# Analog1.net
KiCad netlist of a schematic drawn in Altium Designer
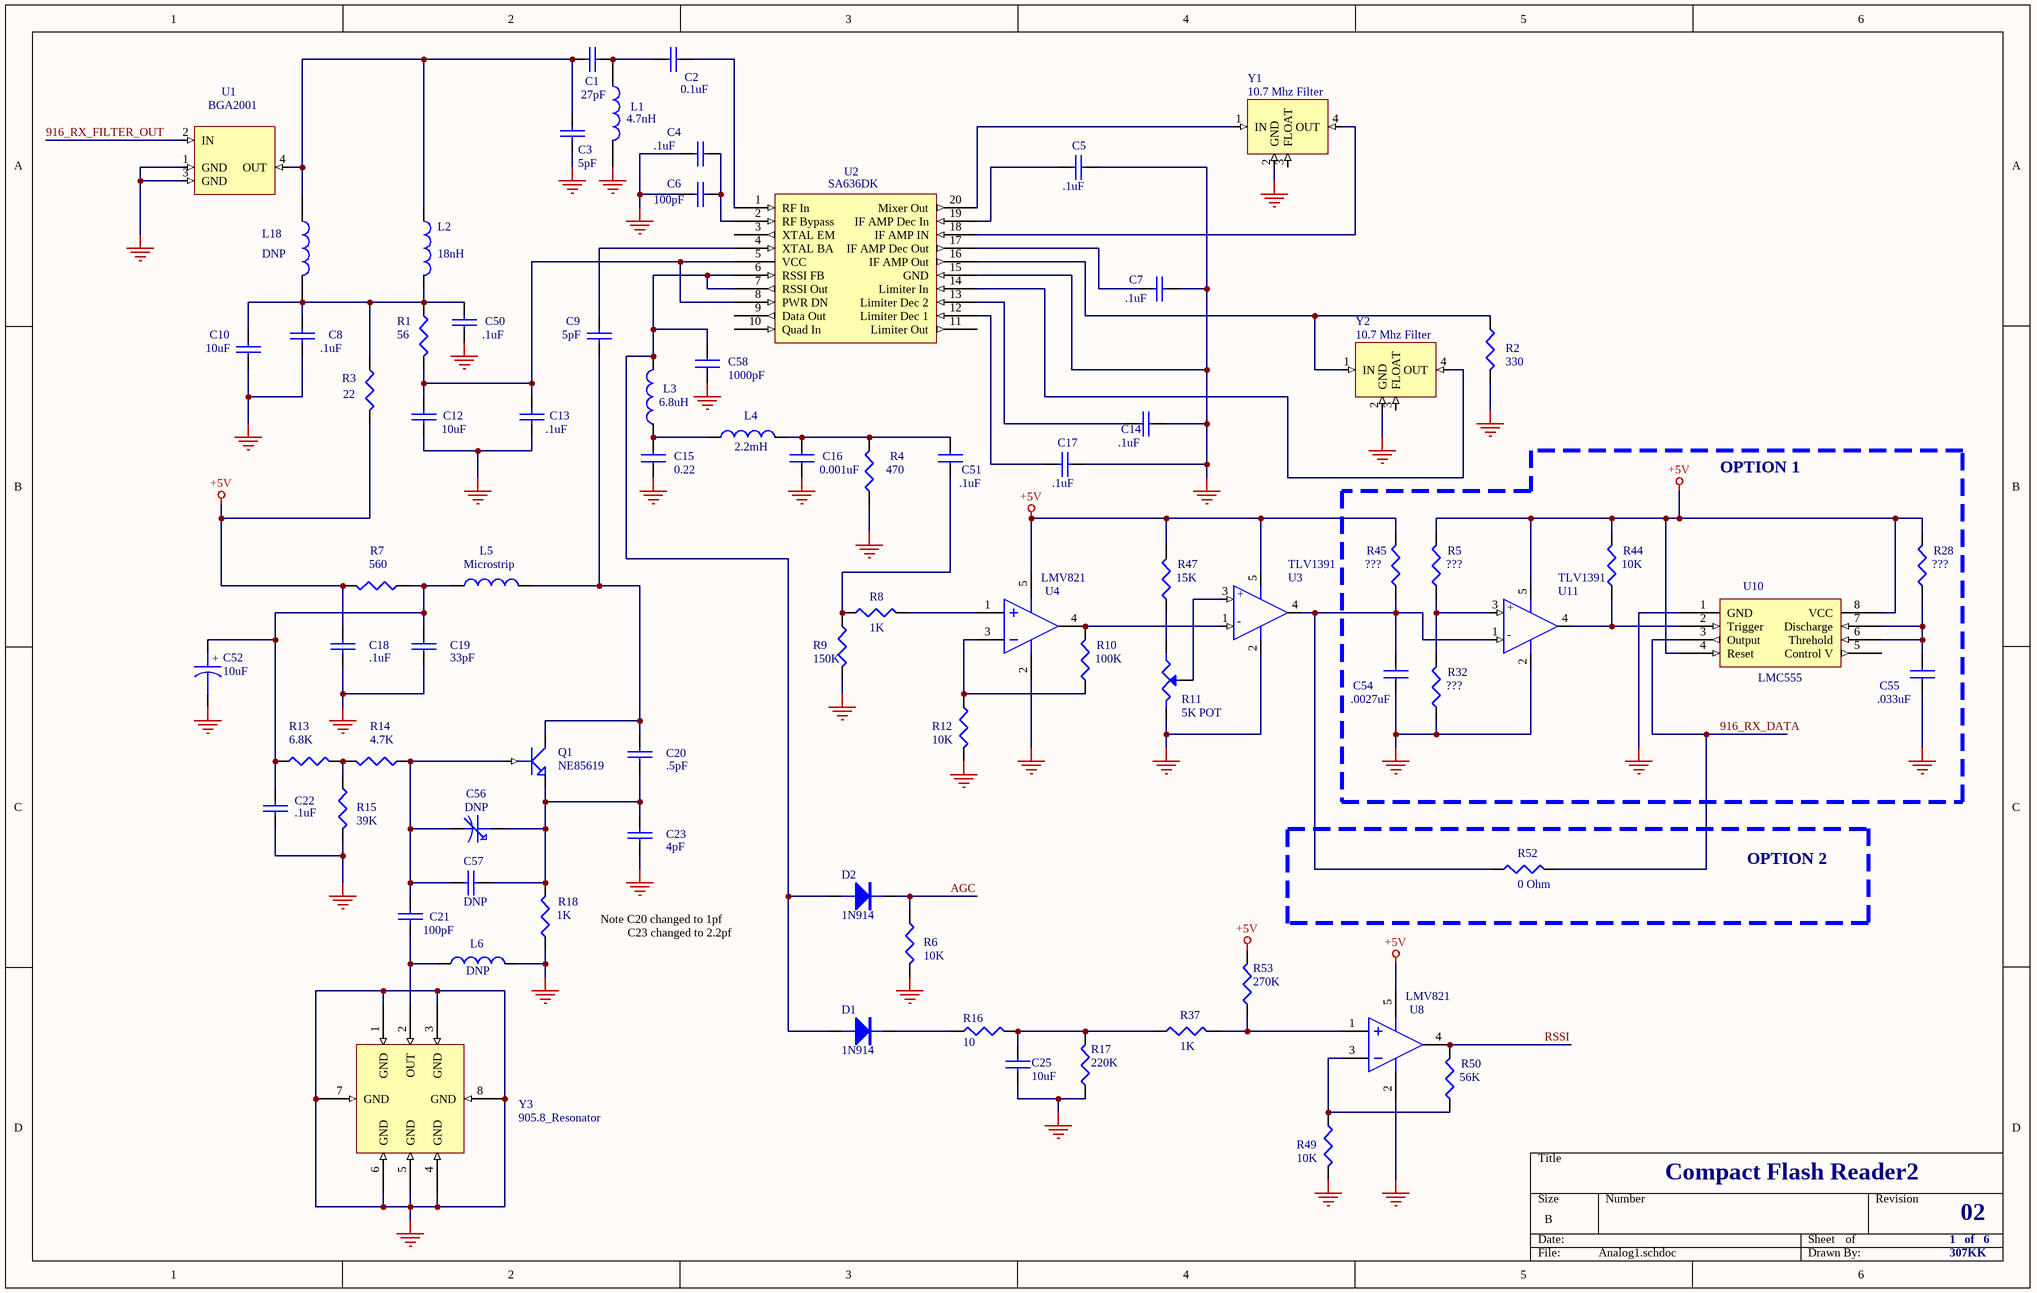
[diagram p0: Analog1.schdoc]

(export (version "E")
  (design (tool "Eeschema 10.0.6"))
  (components
    (comp (ref "C1") (value "27pF") (description "Capacitor") (libsource (lib "*") (part "CAP")))
    (comp (ref "C2") (value "0.1uF") (description "Capacitor") (libsource (lib "*") (part "CAP")))
    (comp (ref "C3") (value "5pF") (description "Capacitor") (libsource (lib "*") (part "CAP")))
    (comp (ref "C4")
      (value ".1uF")
      (footprint "0603")
      (description "Capacitor")
      (libsource (lib "*") (part "CAP"))
    )
    (comp (ref "C5")
      (value ".1uF")
      (footprint "0603")
      (description "Capacitor")
      (libsource (lib "*") (part "CAP"))
    )
    (comp (ref "C6")
      (value "100pF")
      (footprint "0603")
      (description "Capacitor")
      (libsource (lib "*") (part "CAP"))
    )
    (comp (ref "C7")
      (value ".1uF")
      (footprint "0603")
      (description "Capacitor")
      (libsource (lib "*") (part "CAP"))
    )
    (comp (ref "C8")
      (value ".1uF")
      (footprint "0603")
      (description "Capacitor")
      (libsource (lib "*") (part "CAP"))
    )
    (comp (ref "C9")
      (value "5pF")
      (footprint "0603")
      (description "Capacitor")
      (libsource (lib "*") (part "CAP"))
    )
    (comp (ref "C10")
      (value "10uF")
      (footprint "CAP A CASE")
      (description "Capacitor")
      (libsource (lib "*") (part "CAP"))
    )
    (comp (ref "C12")
      (value "10uF")
      (footprint "CAP A CASE")
      (description "Capacitor")
      (libsource (lib "*") (part "CAP"))
    )
    (comp (ref "C13")
      (value ".1uF")
      (footprint "0603")
      (description "Capacitor")
      (libsource (lib "*") (part "CAP"))
    )
    (comp (ref "C14")
      (value ".1uF")
      (footprint "0603")
      (description "Capacitor")
      (libsource (lib "*") (part "CAP"))
    )
    (comp (ref "C15") (value "0.22") (footprint "0603") (libsource (lib "*") (part "CAP_NP")))
    (comp (ref "C16") (value "0.001uF") (footprint "0603") (libsource (lib "*") (part "CAP_NP")))
    (comp (ref "C17")
      (value ".1uF")
      (footprint "0603")
      (description "Capacitor")
      (libsource (lib "*") (part "CAP"))
    )
    (comp (ref "C18")
      (value ".1uF")
      (footprint "0603")
      (description "Capacitor")
      (libsource (lib "*") (part "CAP"))
    )
    (comp (ref "C19")
      (value "33pF")
      (footprint "0603")
      (description "Capacitor")
      (libsource (lib "*") (part "CAP"))
    )
    (comp (ref "C20")
      (value ".5pF")
      (footprint "0603")
      (description "Capacitor")
      (libsource (lib "*") (part "CAP"))
    )
    (comp (ref "C21")
      (value "100pF")
      (footprint "0603")
      (description "Capacitor")
      (libsource (lib "*") (part "CAP"))
    )
    (comp (ref "C22")
      (value ".1uF")
      (footprint "0603")
      (description "Capacitor")
      (libsource (lib "*") (part "CAP"))
    )
    (comp (ref "C23")
      (value "4pF")
      (footprint "0603")
      (description "Capacitor")
      (libsource (lib "*") (part "CAP"))
    )
    (comp (ref "C25") (value "10uF") (footprint "CAP A CASE") (libsource (lib "*") (part "CAP_NP")))
    (comp (ref "C50")
      (value ".1uF")
      (footprint "0603")
      (description "Capacitor")
      (libsource (lib "*") (part "CAP"))
    )
    (comp (ref "C51") (value ".1uF") (footprint "0603") (libsource (lib "*") (part "CAP_NP")))
    (comp (ref "C52")
      (value "10uF")
      (footprint "CAP A CASE")
      (description "Capacitor")
      (libsource (lib "*") (part "CAPACITOR POL"))
    )
    (comp (ref "C54") (value ".0027uF") (footprint "0603") (libsource (lib "*") (part "CAP_NP")))
    (comp (ref "C55") (value ".033uF") (footprint "0805") (libsource (lib "*") (part "CAP_NP")))
    (comp (ref "C56")
      (value "DNP")
      (footprint "CAP TRIMMER JOHANSON")
      (libsource (lib "*") (part "CAPACITOR VAR"))
    )
    (comp (ref "C57")
      (value "DNP")
      (footprint "0603")
      (description "Capacitor")
      (libsource (lib "*") (part "CAP"))
    )
    (comp (ref "C58") (value "1000pF") (footprint "0603") (libsource (lib "*") (part "CAP_NP")))
    (comp (ref "D1")
      (value "1N914")
      (footprint "SOT23 DIODE")
      (description "Diode")
      (libsource (lib "*") (part "DIODE"))
    )
    (comp (ref "D2")
      (value "1N914")
      (footprint "SOT23 DIODE")
      (description "Diode")
      (libsource (lib "*") (part "DIODE"))
    )
    (comp (ref "L1") (value "4.7nH") (libsource (lib "*") (part "INDUCTOR")))
    (comp (ref "L2") (value "18nH") (footprint "0603") (libsource (lib "") (part "INDUCTOR_1")))
    (comp (ref "L3") (value "6.8uH") (footprint "0805") (libsource (lib "") (part "INDUCTOR_1")))
    (comp (ref "L4") (value "2.2mH") (footprint "COIL TKS5540CT-ND") (libsource (lib "") (part "INDUCTOR_1")))
    (comp (ref "L5") (value "Microstrip") (footprint "MICROSTRIP") (libsource (lib "") (part "INDUCTOR_1")))
    (comp (ref "L6") (value "DNP") (footprint "0603") (libsource (lib "") (part "INDUCTOR_1")))
    (comp (ref "L18") (value "DNP") (libsource (lib "*") (part "INDUCTOR")))
    (comp (ref "Q1")
      (value "NE85619")
      (footprint "3 PIN ULTRA SUPER MINI MOLD")
      (description "NPN Transistor")
      (libsource (lib "*") (part "NPN1"))
    )
    (comp (ref "R1") (value "56") (footprint "0603") (libsource (lib "*") (part "R")))
    (comp (ref "R2") (value "330") (footprint "0603") (libsource (lib "*") (part "R")))
    (comp (ref "R3") (value "22") (footprint "0603") (libsource (lib "*") (part "R")))
    (comp (ref "R4") (value "470") (footprint "0603") (libsource (lib "*") (part "R")))
    (comp (ref "R5") (value "???") (footprint "0603") (libsource (lib "*") (part "R")))
    (comp (ref "R6") (value "10K") (footprint "0603") (libsource (lib "*") (part "R")))
    (comp (ref "R7") (value "560") (footprint "0603") (libsource (lib "*") (part "RESISTOR")))
    (comp (ref "R8") (value "1K") (footprint "0603") (libsource (lib "*") (part "R")))
    (comp (ref "R9") (value "150K") (footprint "0603") (libsource (lib "*") (part "R")))
    (comp (ref "R10") (value "100K") (footprint "0603") (libsource (lib "*") (part "R")))
    (comp (ref "R11")
      (value "5K POT")
      (footprint "POT PANA EVN5")
      (description "Potentiometer")
      (libsource (lib "*") (part "POT1"))
    )
    (comp (ref "R12") (value "10K") (footprint "0603") (libsource (lib "*") (part "R")))
    (comp (ref "R13") (value "6.8K") (footprint "0603") (libsource (lib "*") (part "RESISTOR")))
    (comp (ref "R14") (value "4.7K") (footprint "0603") (libsource (lib "*") (part "RESISTOR")))
    (comp (ref "R15") (value "39K") (footprint "0603") (libsource (lib "*") (part "RESISTOR")))
    (comp (ref "R16") (value "10") (footprint "0603") (libsource (lib "*") (part "R")))
    (comp (ref "R17") (value "220K") (footprint "0603") (libsource (lib "*") (part "R")))
    (comp (ref "R18") (value "1K") (footprint "0603") (libsource (lib "*") (part "RESISTOR")))
    (comp (ref "R28") (value "???") (footprint "0603") (libsource (lib "*") (part "R")))
    (comp (ref "R32") (value "???") (footprint "0603") (libsource (lib "*") (part "R")))
    (comp (ref "R37") (value "1K") (footprint "0603") (libsource (lib "*") (part "R")))
    (comp (ref "R44") (value "10K") (footprint "0603") (libsource (lib "*") (part "R")))
    (comp (ref "R45") (value "???") (footprint "0603") (libsource (lib "*") (part "R")))
    (comp (ref "R47") (value "15K") (footprint "0603") (libsource (lib "*") (part "R")))
    (comp (ref "R49") (value "10K") (footprint "0603") (libsource (lib "*") (part "R")))
    (comp (ref "R50") (value "56K") (footprint "0603") (libsource (lib "*") (part "R")))
    (comp (ref "R52") (value "0 Ohm") (footprint "0603") (libsource (lib "*") (part "R")))
    (comp (ref "R53") (value "270K") (footprint "0603") (libsource (lib "*") (part "R")))
    (comp (ref "U1") (value "BGA2001") (footprint "SOT343") (libsource (lib "*") (part "BGA2001")))
    (comp (ref "U2") (value "SA636DK") (footprint "SSOP20") (libsource (lib "*") (part "SA636DK")))
    (comp (ref "U3") (value "TLV1391") (footprint "SOT25") (libsource (lib "*") (part "TLV1391")))
    (comp (ref "U4") (value "LMV821") (footprint "SOT25") (libsource (lib "*") (part "OPAMP1")))
    (comp (ref "U8") (value "LMV821") (footprint "SOT25") (libsource (lib "*") (part "OPAMP1")))
    (comp (ref "U10") (value "LMC555") (footprint "SO8 SMALL") (libsource (lib "*") (part "LMC555")))
    (comp (ref "U11") (value "TLV1391") (footprint "SOT25") (libsource (lib "*") (part "TLV1391")))
    (comp (ref "Y1") (value "10.7 Mhz Filter") (footprint "FILTER2") (libsource (lib "*") (part "FILTER2")))
    (comp (ref "Y2") (value "10.7 Mhz Filter") (footprint "FILTER2") (libsource (lib "*") (part "FILTER2")))
    (comp (ref "Y3")
      (value "905.8_Resonator")
      (footprint "RESONATOR2")
      (libsource (lib "Compact Flash Reader2") (part "RESONATOR2"))
    )
  )
  (nets
    (net (code "1") (name "+5V") (class "Default")
      (node (ref "C18") (pin "1") (pinfunction "1_1") (pintype "passive"))
      (node (ref "R28") (pin "2") (pinfunction "2_2") (pintype "passive"))
      (node (ref "R3") (pin "2") (pinfunction "2_2") (pintype "passive"))
      (node (ref "R44") (pin "2") (pinfunction "2_2") (pintype "passive"))
      (node (ref "R45") (pin "2") (pinfunction "2_2") (pintype "passive"))
      (node (ref "R47") (pin "2") (pinfunction "2_2") (pintype "passive"))
      (node (ref "R5") (pin "2") (pinfunction "2_2") (pintype "passive"))
      (node (ref "R53") (pin "2") (pinfunction "2_2") (pintype "passive"))
      (node (ref "R7") (pin "2") (pinfunction "2_2") (pintype "passive"))
      (node (ref "U10") (pin "4") (pinfunction "Reset_4") (pintype "input"))
      (node (ref "U10") (pin "8") (pinfunction "VCC_8") (pintype "power_in"))
      (node (ref "U11") (pin "5") (pinfunction "VDD_5") (pintype "power_in"))
      (node (ref "U3") (pin "5") (pinfunction "VDD_5") (pintype "power_in"))
      (node (ref "U4") (pin "5") (pinfunction "5_5") (pintype "passive"))
      (node (ref "U8") (pin "5") (pinfunction "5_5") (pintype "passive"))
    )
    (net (code "2") (name "/916_RX_DATA") (class "Default")
      (node (ref "R52") (pin "2") (pinfunction "2_2") (pintype "passive"))
      (node (ref "U10") (pin "3") (pinfunction "Output_3") (pintype "output"))
    )
    (net (code "3") (name "/916_RX_FILTER_OUT") (class "Default")
      (node (ref "U1") (pin "2") (pinfunction "IN_2") (pintype "input"))
    )
    (net (code "4") (name "/AGC") (class "Default")
      (node (ref "D2") (pin "K") (pinfunction "K_K") (pintype "passive"))
      (node (ref "R6") (pin "1") (pinfunction "1_1") (pintype "passive"))
    )
    (net (code "5") (name "/RSSI") (class "Default")
      (node (ref "R50") (pin "2") (pinfunction "2_2") (pintype "passive"))
      (node (ref "U8") (pin "4") (pinfunction "4_4") (pintype "passive"))
    )
    (net (code "6") (name "GND_SIGNAL") (class "Default")
      (node (ref "C10") (pin "2") (pinfunction "2_2") (pintype "passive"))
      (node (ref "C12") (pin "2") (pinfunction "2_2") (pintype "passive"))
      (node (ref "C13") (pin "2") (pinfunction "2_2") (pintype "passive"))
      (node (ref "C14") (pin "2") (pinfunction "2_2") (pintype "passive"))
      (node (ref "C15") (pin "1") (pinfunction "1_1") (pintype "passive"))
      (node (ref "C16") (pin "1") (pinfunction "1_1") (pintype "passive"))
      (node (ref "C17") (pin "2") (pinfunction "2_2") (pintype "passive"))
      (node (ref "C18") (pin "2") (pinfunction "2_2") (pintype "passive"))
      (node (ref "C19") (pin "2") (pinfunction "2_2") (pintype "passive"))
      (node (ref "C22") (pin "2") (pinfunction "2_2") (pintype "passive"))
      (node (ref "C23") (pin "2") (pinfunction "2_2") (pintype "passive"))
      (node (ref "C25") (pin "2") (pinfunction "2_2") (pintype "passive"))
      (node (ref "C3") (pin "2") (pinfunction "2_2") (pintype "passive"))
      (node (ref "C4") (pin "1") (pinfunction "1_1") (pintype "passive"))
      (node (ref "C5") (pin "2") (pinfunction "2_2") (pintype "passive"))
      (node (ref "C50") (pin "2") (pinfunction "2_2") (pintype "passive"))
      (node (ref "C52") (pin "2") (pinfunction "2_2") (pintype "passive"))
      (node (ref "C54") (pin "1") (pinfunction "1_1") (pintype "passive"))
      (node (ref "C55") (pin "1") (pinfunction "1_1") (pintype "passive"))
      (node (ref "C58") (pin "1") (pinfunction "1_1") (pintype "passive"))
      (node (ref "C6") (pin "1") (pinfunction "1_1") (pintype "passive"))
      (node (ref "C7") (pin "2") (pinfunction "2_2") (pintype "passive"))
      (node (ref "C8") (pin "2") (pinfunction "2_2") (pintype "passive"))
      (node (ref "L1") (pin "2") (pinfunction "2_2") (pintype "passive"))
      (node (ref "L6") (pin "2") (pinfunction "2_2") (pintype "passive"))
      (node (ref "R11") (pin "3") (pinfunction "3_3") (pintype "passive"))
      (node (ref "R12") (pin "2") (pinfunction "2_2") (pintype "passive"))
      (node (ref "R15") (pin "2") (pinfunction "2_2") (pintype "passive"))
      (node (ref "R17") (pin "2") (pinfunction "2_2") (pintype "passive"))
      (node (ref "R18") (pin "1") (pinfunction "1_1") (pintype "passive"))
      (node (ref "R2") (pin "2") (pinfunction "2_2") (pintype "passive"))
      (node (ref "R32") (pin "1") (pinfunction "1_1") (pintype "passive"))
      (node (ref "R4") (pin "1") (pinfunction "1_1") (pintype "passive"))
      (node (ref "R49") (pin "2") (pinfunction "2_2") (pintype "passive"))
      (node (ref "R6") (pin "2") (pinfunction "2_2") (pintype "passive"))
      (node (ref "R9") (pin "2") (pinfunction "2_2") (pintype "passive"))
      (node (ref "U1") (pin "1") (pinfunction "GND_1") (pintype "input"))
      (node (ref "U1") (pin "3") (pinfunction "GND_3") (pintype "input"))
      (node (ref "U10") (pin "1") (pinfunction "GND_1") (pintype "power_in"))
      (node (ref "U11") (pin "2") (pinfunction "VSS_2") (pintype "power_in"))
      (node (ref "U2") (pin "15") (pinfunction "GND_15") (pintype "input"))
      (node (ref "U3") (pin "2") (pinfunction "VSS_2") (pintype "power_in"))
      (node (ref "U4") (pin "2") (pinfunction "2_2") (pintype "passive"))
      (node (ref "U8") (pin "2") (pinfunction "2_2") (pintype "passive"))
      (node (ref "Y1") (pin "2") (pinfunction "GND_2") (pintype "input"))
      (node (ref "Y2") (pin "2") (pinfunction "GND_2") (pintype "input"))
      (node (ref "Y3") (pin "1") (pinfunction "GND_1") (pintype "input"))
      (node (ref "Y3") (pin "3") (pinfunction "GND_3") (pintype "input"))
      (node (ref "Y3") (pin "4") (pinfunction "GND_4") (pintype "input"))
      (node (ref "Y3") (pin "5") (pinfunction "GND_5") (pintype "input"))
      (node (ref "Y3") (pin "6") (pinfunction "GND_6") (pintype "input"))
      (node (ref "Y3") (pin "7") (pinfunction "GND_7") (pintype "input"))
      (node (ref "Y3") (pin "8") (pinfunction "GND_8") (pintype "input"))
    )
    (net (code "7") (name "Net-(C1-Pad2)") (class "Default")
      (node (ref "C1") (pin "2") (pinfunction "2_2") (pintype "passive"))
      (node (ref "C2") (pin "1") (pinfunction "1_1") (pintype "passive"))
      (node (ref "L1") (pin "1") (pinfunction "1_1") (pintype "passive"))
    )
    (net (code "8") (name "Net-(C10-Pad1)") (class "Default")
      (node (ref "C10") (pin "1") (pinfunction "1_1") (pintype "passive"))
      (node (ref "C50") (pin "1") (pinfunction "1_1") (pintype "passive"))
      (node (ref "C8") (pin "1") (pinfunction "1_1") (pintype "passive"))
      (node (ref "L18") (pin "2") (pinfunction "2_2") (pintype "passive"))
      (node (ref "L2") (pin "2") (pinfunction "2_2") (pintype "passive"))
      (node (ref "R1") (pin "1") (pinfunction "1_1") (pintype "passive"))
      (node (ref "R3") (pin "1") (pinfunction "1_1") (pintype "passive"))
    )
    (net (code "9") (name "Net-(C15-Pad2)") (class "Default")
      (node (ref "C15") (pin "2") (pinfunction "2_2") (pintype "passive"))
      (node (ref "L3") (pin "1") (pinfunction "1_1") (pintype "passive"))
      (node (ref "L4") (pin "1") (pinfunction "1_1") (pintype "passive"))
    )
    (net (code "10") (name "Net-(C16-Pad2)") (class "Default")
      (node (ref "C16") (pin "2") (pinfunction "2_2") (pintype "passive"))
      (node (ref "C51") (pin "2") (pinfunction "2_2") (pintype "passive"))
      (node (ref "L4") (pin "2") (pinfunction "2_2") (pintype "passive"))
      (node (ref "R4") (pin "2") (pinfunction "2_2") (pintype "passive"))
    )
    (net (code "11") (name "Net-(C19-Pad1)") (class "Default")
      (node (ref "C19") (pin "1") (pinfunction "1_1") (pintype "passive"))
      (node (ref "C22") (pin "1") (pinfunction "1_1") (pintype "passive"))
      (node (ref "C52") (pin "1") (pinfunction "1_1") (pintype "passive"))
      (node (ref "L5") (pin "1") (pinfunction "1_1") (pintype "passive"))
      (node (ref "R13") (pin "1") (pinfunction "1_1") (pintype "passive"))
      (node (ref "R7") (pin "1") (pinfunction "1_1") (pintype "passive"))
    )
    (net (code "12") (name "Net-(C20-Pad1)") (class "Default")
      (node (ref "C20") (pin "1") (pinfunction "1_1") (pintype "passive"))
      (node (ref "C9") (pin "1") (pinfunction "1_1") (pintype "passive"))
      (node (ref "L5") (pin "2") (pinfunction "2_2") (pintype "passive"))
      (node (ref "Q1") (pin "C") (pinfunction "C_C") (pintype "passive"))
    )
    (net (code "13") (name "Net-(C20-Pad2)") (class "Default")
      (node (ref "C20") (pin "2") (pinfunction "2_2") (pintype "passive"))
      (node (ref "C23") (pin "1") (pinfunction "1_1") (pintype "passive"))
      (node (ref "C56") (pin "1") (pinfunction "1_1") (pintype "passive"))
      (node (ref "C57") (pin "2") (pinfunction "2_2") (pintype "passive"))
      (node (ref "Q1") (pin "E") (pinfunction "E_E") (pintype "passive"))
      (node (ref "R18") (pin "2") (pinfunction "2_2") (pintype "passive"))
    )
    (net (code "14") (name "Net-(C21-Pad1)") (class "Default")
      (node (ref "C21") (pin "1") (pinfunction "1_1") (pintype "passive"))
      (node (ref "C56") (pin "2") (pinfunction "2_2") (pintype "passive"))
      (node (ref "C57") (pin "1") (pinfunction "1_1") (pintype "passive"))
      (node (ref "Q1") (pin "B") (pinfunction "B_B") (pintype "input"))
      (node (ref "R14") (pin "1") (pinfunction "1_1") (pintype "passive"))
    )
    (net (code "15") (name "Net-(C25-Pad1)") (class "Default")
      (node (ref "C25") (pin "1") (pinfunction "1_1") (pintype "passive"))
      (node (ref "R16") (pin "1") (pinfunction "1_1") (pintype "passive"))
      (node (ref "R17") (pin "1") (pinfunction "1_1") (pintype "passive"))
      (node (ref "R37") (pin "1") (pinfunction "1_1") (pintype "passive"))
    )
    (net (code "16") (name "Net-(C51-Pad1)") (class "Default")
      (node (ref "C51") (pin "1") (pinfunction "1_1") (pintype "passive"))
      (node (ref "R8") (pin "1") (pinfunction "1_1") (pintype "passive"))
      (node (ref "R9") (pin "1") (pinfunction "1_1") (pintype "passive"))
    )
    (net (code "17") (name "Net-(D1-PadK)") (class "Default")
      (node (ref "D1") (pin "K") (pinfunction "K_K") (pintype "passive"))
      (node (ref "R16") (pin "2") (pinfunction "2_2") (pintype "passive"))
    )
    (net (code "18") (name "Net-(R8-Pad2)") (class "Default")
      (node (ref "R8") (pin "2") (pinfunction "2_2") (pintype "passive"))
      (node (ref "U4") (pin "1") (pinfunction "1_1") (pintype "passive"))
    )
    (net (code "19") (name "Net-(R10-Pad1)") (class "Default")
      (node (ref "R10") (pin "1") (pinfunction "1_1") (pintype "passive"))
      (node (ref "R12") (pin "1") (pinfunction "1_1") (pintype "passive"))
      (node (ref "U4") (pin "3") (pinfunction "3_3") (pintype "passive"))
    )
    (net (code "20") (name "Net-(R11-Pad1)") (class "Default")
      (node (ref "R11") (pin "1") (pinfunction "1_1") (pintype "passive"))
      (node (ref "R47") (pin "1") (pinfunction "1_1") (pintype "passive"))
    )
    (net (code "21") (name "Net-(R13-Pad2)") (class "Default")
      (node (ref "R13") (pin "2") (pinfunction "2_2") (pintype "passive"))
      (node (ref "R14") (pin "2") (pinfunction "2_2") (pintype "passive"))
      (node (ref "R15") (pin "1") (pinfunction "1_1") (pintype "passive"))
    )
    (net (code "22") (name "Net-(R37-Pad2)") (class "Default")
      (node (ref "R37") (pin "2") (pinfunction "2_2") (pintype "passive"))
      (node (ref "R53") (pin "1") (pinfunction "1_1") (pintype "passive"))
      (node (ref "U8") (pin "1") (pinfunction "1_1") (pintype "passive"))
    )
    (net (code "23") (name "Net-(R49-Pad1)") (class "Default")
      (node (ref "R49") (pin "1") (pinfunction "1_1") (pintype "passive"))
      (node (ref "R50") (pin "1") (pinfunction "1_1") (pintype "passive"))
      (node (ref "U8") (pin "3") (pinfunction "3_3") (pintype "passive"))
    )
    (net (code "24") (name "Net-(U1-OUT)") (class "Default")
      (node (ref "C1") (pin "1") (pinfunction "1_1") (pintype "passive"))
      (node (ref "C3") (pin "1") (pinfunction "1_1") (pintype "passive"))
      (node (ref "L18") (pin "1") (pinfunction "1_1") (pintype "passive"))
      (node (ref "L2") (pin "1") (pinfunction "1_1") (pintype "passive"))
      (node (ref "U1") (pin "4") (pinfunction "OUT_4") (pintype "input"))
    )
    (net (code "25") (name "Net-(U2-IF_AMP_Dec_In)") (class "Default")
      (node (ref "C5") (pin "1") (pinfunction "1_1") (pintype "passive"))
      (node (ref "U2") (pin "19") (pinfunction "IF_AMP_Dec_In_19") (pintype "input"))
    )
    (net (code "26") (name "Net-(U2-IF_AMP_Dec_Out)") (class "Default")
      (node (ref "C7") (pin "1") (pinfunction "1_1") (pintype "passive"))
      (node (ref "U2") (pin "17") (pinfunction "IF_AMP_Dec_Out_17") (pintype "output"))
    )
    (net (code "27") (name "Net-(U2-IF_AMP_IN)") (class "Default")
      (node (ref "U2") (pin "18") (pinfunction "IF_AMP_IN_18") (pintype "input"))
      (node (ref "Y1") (pin "4") (pinfunction "OUT_4") (pintype "input"))
    )
    (net (code "28") (name "Net-(U2-IF_AMP_Out)") (class "Default")
      (node (ref "R2") (pin "1") (pinfunction "1_1") (pintype "passive"))
      (node (ref "U2") (pin "16") (pinfunction "IF_AMP_Out_16") (pintype "output"))
      (node (ref "Y2") (pin "1") (pinfunction "IN_1") (pintype "input"))
    )
    (net (code "29") (name "Net-(U2-Limiter_Dec_1)") (class "Default")
      (node (ref "C17") (pin "1") (pinfunction "1_1") (pintype "passive"))
      (node (ref "U2") (pin "12") (pinfunction "Limiter_Dec_1_12") (pintype "input"))
    )
    (net (code "30") (name "Net-(U2-Limiter_Dec_2)") (class "Default")
      (node (ref "C14") (pin "1") (pinfunction "1_1") (pintype "passive"))
      (node (ref "U2") (pin "13") (pinfunction "Limiter_Dec_2_13") (pintype "input"))
    )
    (net (code "31") (name "Net-(U2-Limiter_In)") (class "Default")
      (node (ref "U2") (pin "14") (pinfunction "Limiter_In_14") (pintype "input"))
      (node (ref "Y2") (pin "4") (pinfunction "OUT_4") (pintype "input"))
    )
    (net (code "32") (name "Net-(U2-Mixer_Out)") (class "Default")
      (node (ref "U2") (pin "20") (pinfunction "Mixer_Out_20") (pintype "output"))
      (node (ref "Y1") (pin "1") (pinfunction "IN_1") (pintype "input"))
    )
    (net (code "33") (name "Net-(U2-PWR_DN)") (class "Default")
      (node (ref "C12") (pin "1") (pinfunction "1_1") (pintype "passive"))
      (node (ref "C13") (pin "1") (pinfunction "1_1") (pintype "passive"))
      (node (ref "R1") (pin "2") (pinfunction "2_2") (pintype "passive"))
      (node (ref "U2") (pin "5") (pinfunction "VCC_5") (pintype "power_in"))
      (node (ref "U2") (pin "8") (pinfunction "PWR_DN_8") (pintype "input"))
    )
    (net (code "34") (name "Net-(U2-RF_Bypass)") (class "Default")
      (node (ref "C4") (pin "2") (pinfunction "2_2") (pintype "passive"))
      (node (ref "C6") (pin "2") (pinfunction "2_2") (pintype "passive"))
      (node (ref "U2") (pin "2") (pinfunction "RF_Bypass_2") (pintype "input"))
    )
    (net (code "35") (name "Net-(U2-RF_In)") (class "Default")
      (node (ref "C2") (pin "2") (pinfunction "2_2") (pintype "passive"))
      (node (ref "U2") (pin "1") (pinfunction "RF_In_1") (pintype "input"))
    )
    (net (code "36") (name "Net-(U2-RSSI_FB)") (class "Default")
      (node (ref "C58") (pin "2") (pinfunction "2_2") (pintype "passive"))
      (node (ref "D1") (pin "A") (pinfunction "A_A") (pintype "passive"))
      (node (ref "D2") (pin "A") (pinfunction "A_A") (pintype "passive"))
      (node (ref "L3") (pin "2") (pinfunction "2_2") (pintype "passive"))
      (node (ref "U2") (pin "6") (pinfunction "RSSI_FB_6") (pintype "input"))
      (node (ref "U2") (pin "7") (pinfunction "RSSI_Out_7") (pintype "output"))
    )
    (net (code "37") (name "Net-(U2-XTAL_BA)") (class "Default")
      (node (ref "C9") (pin "2") (pinfunction "2_2") (pintype "passive"))
      (node (ref "U2") (pin "4") (pinfunction "XTAL_BA_4") (pintype "input"))
    )
    (net (code "38") (name "Net-(U3-+)") (class "Default")
      (node (ref "R11") (pin "2") (pinfunction "2_2") (pintype "passive"))
      (node (ref "U3") (pin "3") (pinfunction "+_3") (pintype "input"))
    )
    (net (code "39") (name "Net-(U3--)") (class "Default")
      (node (ref "R10") (pin "2") (pinfunction "2_2") (pintype "passive"))
      (node (ref "U3") (pin "1") (pinfunction "-_1") (pintype "input"))
      (node (ref "U4") (pin "4") (pinfunction "4_4") (pintype "passive"))
    )
    (net (code "40") (name "Net-(U10-Discharge)") (class "Default")
      (node (ref "C55") (pin "2") (pinfunction "2_2") (pintype "passive"))
      (node (ref "R28") (pin "1") (pinfunction "1_1") (pintype "passive"))
      (node (ref "U10") (pin "6") (pinfunction "Threhold_6") (pintype "input"))
      (node (ref "U10") (pin "7") (pinfunction "Discharge_7") (pintype "input"))
    )
    (net (code "41") (name "Net-(U10-Trigger)") (class "Default")
      (node (ref "R44") (pin "1") (pinfunction "1_1") (pintype "passive"))
      (node (ref "U10") (pin "2") (pinfunction "Trigger_2") (pintype "input"))
      (node (ref "U11") (pin "4") (pinfunction "OUT_4") (pintype "open_collector"))
    )
    (net (code "42") (name "Net-(U11-+)") (class "Default")
      (node (ref "R32") (pin "2") (pinfunction "2_2") (pintype "passive"))
      (node (ref "R5") (pin "1") (pinfunction "1_1") (pintype "passive"))
      (node (ref "U11") (pin "3") (pinfunction "+_3") (pintype "input"))
    )
    (net (code "43") (name "Net-(U11--)") (class "Default")
      (node (ref "C54") (pin "2") (pinfunction "2_2") (pintype "passive"))
      (node (ref "R45") (pin "1") (pinfunction "1_1") (pintype "passive"))
      (node (ref "R52") (pin "1") (pinfunction "1_1") (pintype "passive"))
      (node (ref "U11") (pin "1") (pinfunction "-_1") (pintype "input"))
      (node (ref "U3") (pin "4") (pinfunction "OUT_4") (pintype "open_collector"))
    )
    (net (code "44") (name "Net-(Y3-OUT)") (class "Default")
      (node (ref "C21") (pin "2") (pinfunction "2_2") (pintype "passive"))
      (node (ref "L6") (pin "1") (pinfunction "1_1") (pintype "passive"))
      (node (ref "Y3") (pin "2") (pinfunction "OUT_2") (pintype "input"))
    )
    (net (code "45") (name "unconnected-(U2-Data_Out-Pad9)") (class "Default")
      (node (ref "U2") (pin "9") (pinfunction "Data_Out_9") (pintype "output"))
    )
    (net (code "46") (name "unconnected-(U2-Limiter_Out-Pad11)") (class "Default")
      (node (ref "U2") (pin "11") (pinfunction "Limiter_Out_11") (pintype "output"))
    )
    (net (code "47") (name "unconnected-(U2-Quad_In-Pad10)") (class "Default")
      (node (ref "U2") (pin "10") (pinfunction "Quad_In_10") (pintype "input"))
    )
    (net (code "48") (name "unconnected-(U2-XTAL_EM-Pad3)") (class "Default")
      (node (ref "U2") (pin "3") (pinfunction "XTAL_EM_3") (pintype "output"))
    )
    (net (code "49") (name "unconnected-(U10-Control_V-Pad5)") (class "Default")
      (node (ref "U10") (pin "5") (pinfunction "Control_V_5") (pintype "output"))
    )
    (net (code "50") (name "unconnected-(Y1-FLOAT-Pad3)") (class "Default")
      (node (ref "Y1") (pin "3") (pinfunction "FLOAT_3") (pintype "input"))
    )
    (net (code "51") (name "unconnected-(Y2-FLOAT-Pad3)") (class "Default")
      (node (ref "Y2") (pin "3") (pinfunction "FLOAT_3") (pintype "input"))
    )
  )
)
